# base.net
KiCad netlist of a schematic drawn in EAGLE
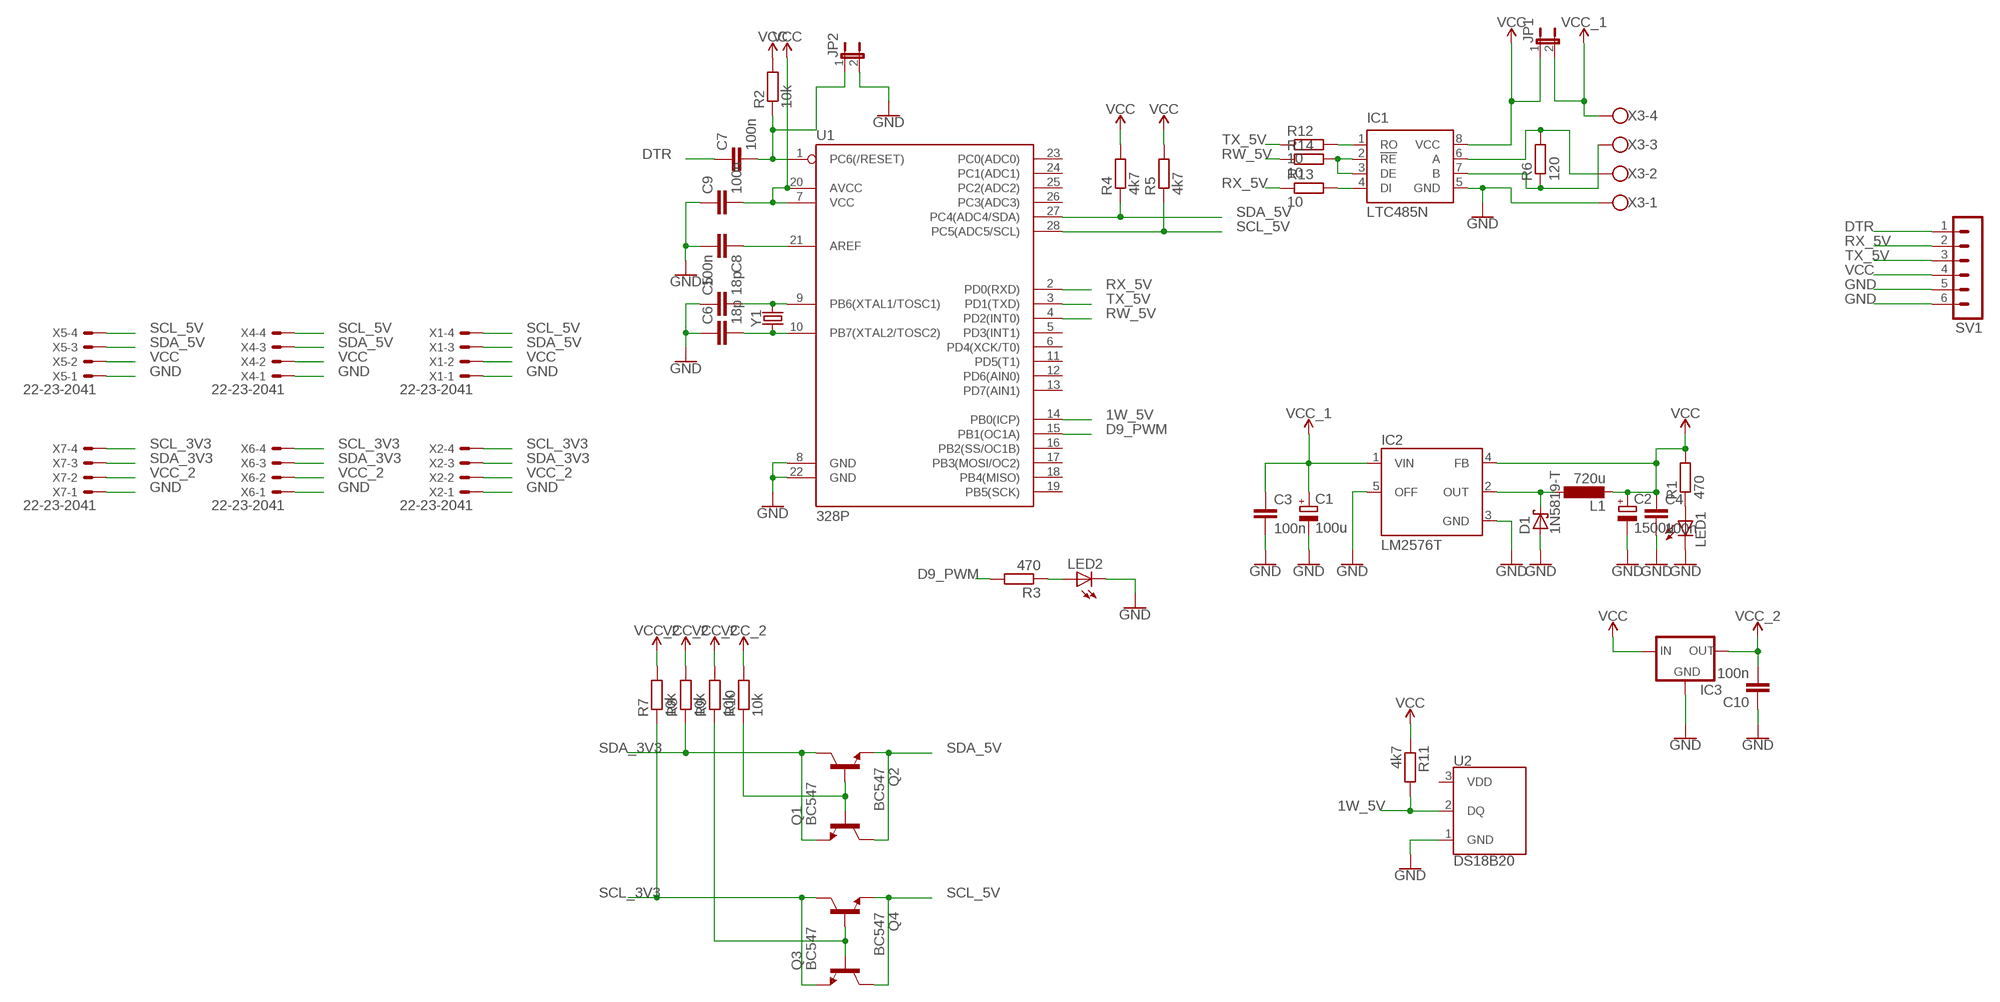
[diagram p0: schematic, sheet 1]

(export (version "E")
  (design (tool "Eeschema 10.0.6"))
  (components
    (comp (ref "C1")
      (value "100u")
      (footprint "eagle-import:E5-10,5")
      (libsource (lib "eagle-import") (part "CPOL-EUE5-10.5"))
    )
    (comp (ref "C2")
      (value "1500u")
      (footprint "eagle-import:E5-10,5")
      (libsource (lib "eagle-import") (part "CPOL-EUE5-10.5"))
    )
    (comp (ref "C3")
      (value "100n")
      (footprint "eagle-import:C025-025X050")
      (libsource (lib "eagle-import") (part "C-EU025-025X050"))
    )
    (comp (ref "C4")
      (value "100n")
      (footprint "eagle-import:C025-025X050")
      (libsource (lib "eagle-import") (part "C-EU025-025X050"))
    )
    (comp (ref "C5")
      (value "18p")
      (footprint "eagle-import:C025-025X050")
      (libsource (lib "eagle-import") (part "C-EU025-025X050"))
    )
    (comp (ref "C6")
      (value "18p")
      (footprint "eagle-import:C025-025X050")
      (libsource (lib "eagle-import") (part "C-EU025-025X050"))
    )
    (comp (ref "C7")
      (value "100n")
      (footprint "eagle-import:C025-025X050")
      (libsource (lib "eagle-import") (part "C-EU025-025X050"))
    )
    (comp (ref "C8")
      (value "100n")
      (footprint "eagle-import:C025-025X050")
      (libsource (lib "eagle-import") (part "C-EU025-025X050"))
    )
    (comp (ref "C9")
      (value "100n")
      (footprint "eagle-import:C025-025X050")
      (libsource (lib "eagle-import") (part "C-EU025-025X050"))
    )
    (comp (ref "C10")
      (value "100n")
      (footprint "eagle-import:C025-025X050")
      (libsource (lib "eagle-import") (part "C-EU025-025X050"))
    )
    (comp (ref "D1")
      (value "1N5819-T")
      (footprint "eagle-import:DO41-7.6")
      (libsource (lib "eagle-import") (part "1N5819-T"))
    )
    (comp (ref "IC1")
      (value "LTC485N")
      (footprint "eagle-import:DIL08")
      (libsource (lib "eagle-import") (part "LTC485N"))
    )
    (comp (ref "IC2")
      (value "LM2576T")
      (footprint "eagle-import:TO220-5")
      (libsource (lib "eagle-import") (part "LM2576T"))
    )
    (comp (ref "IC3")
      (value "78LXX-SOT89")
      (footprint "eagle-import:SOT89")
      (libsource (lib "eagle-import") (part "78LXX-SOT89"))
    )
    (comp (ref "JP1")
      (value "JP1E")
      (footprint "eagle-import:JP1")
      (libsource (lib "eagle-import") (part "JP1E"))
    )
    (comp (ref "JP2")
      (value "JP1E")
      (footprint "eagle-import:JP1")
      (libsource (lib "eagle-import") (part "JP1E"))
    )
    (comp (ref "L1")
      (value "720u")
      (footprint "eagle-import:TJ3-U1")
      (libsource (lib "eagle-import") (part "L-EUTJ3-U1"))
    )
    (comp (ref "LED1")
      (value "LED5MM")
      (footprint "eagle-import:LED5MM")
      (libsource (lib "eagle-import") (part "LED5MM"))
    )
    (comp (ref "LED2")
      (value "LED5MM")
      (footprint "eagle-import:LED5MM")
      (libsource (lib "eagle-import") (part "LED5MM"))
    )
    (comp (ref "Q1")
      (value "BC547")
      (footprint "eagle-import:TO92")
      (libsource (lib "eagle-import") (part "BC547"))
    )
    (comp (ref "Q2")
      (value "BC547")
      (footprint "eagle-import:TO92")
      (libsource (lib "eagle-import") (part "BC547"))
    )
    (comp (ref "Q3")
      (value "BC547")
      (footprint "eagle-import:TO92")
      (libsource (lib "eagle-import") (part "BC547"))
    )
    (comp (ref "Q4")
      (value "BC547")
      (footprint "eagle-import:TO92")
      (libsource (lib "eagle-import") (part "BC547"))
    )
    (comp (ref "R1")
      (value "470")
      (footprint "eagle-import:0204_7")
      (libsource (lib "eagle-import") (part "R-EU_0204/7"))
    )
    (comp (ref "R2")
      (value "10k")
      (footprint "eagle-import:0204_7")
      (libsource (lib "eagle-import") (part "R-EU_0204/7"))
    )
    (comp (ref "R3")
      (value "470")
      (footprint "eagle-import:0204_7")
      (libsource (lib "eagle-import") (part "R-EU_0204/7"))
    )
    (comp (ref "R4")
      (value "4k7")
      (footprint "eagle-import:0204_7")
      (libsource (lib "eagle-import") (part "R-EU_0204/7"))
    )
    (comp (ref "R5")
      (value "4k7")
      (footprint "eagle-import:0204_7")
      (libsource (lib "eagle-import") (part "R-EU_0204/7"))
    )
    (comp (ref "R6")
      (value "120")
      (footprint "eagle-import:0204_7")
      (libsource (lib "eagle-import") (part "R-EU_0204/7"))
    )
    (comp (ref "R7")
      (value "10k")
      (footprint "eagle-import:0204_7")
      (libsource (lib "eagle-import") (part "R-EU_0204/7"))
    )
    (comp (ref "R8")
      (value "10k")
      (footprint "eagle-import:0204_7")
      (libsource (lib "eagle-import") (part "R-EU_0204/7"))
    )
    (comp (ref "R9")
      (value "10k")
      (footprint "eagle-import:0204_7")
      (libsource (lib "eagle-import") (part "R-EU_0204/7"))
    )
    (comp (ref "R10")
      (value "10k")
      (footprint "eagle-import:0204_7")
      (libsource (lib "eagle-import") (part "R-EU_0204/7"))
    )
    (comp (ref "R11")
      (value "4k7")
      (footprint "eagle-import:0204_7")
      (libsource (lib "eagle-import") (part "R-EU_0204/7"))
    )
    (comp (ref "R12")
      (value "10")
      (footprint "eagle-import:0204_7")
      (libsource (lib "eagle-import") (part "R-EU_0204/7"))
    )
    (comp (ref "R13")
      (value "10")
      (footprint "eagle-import:0204_7")
      (libsource (lib "eagle-import") (part "R-EU_0204/7"))
    )
    (comp (ref "R14")
      (value "10")
      (footprint "eagle-import:0204_7")
      (libsource (lib "eagle-import") (part "R-EU_0204/7"))
    )
    (comp (ref "SV1")
      (value "MA06-1")
      (footprint "eagle-import:MA06-1")
      (libsource (lib "eagle-import") (part "MA06-1"))
    )
    (comp (ref "U1")
      (value "328P")
      (footprint "eagle-import:DIP28")
      (libsource (lib "eagle-import") (part "ATMEGA328P_PDIP"))
    )
    (comp (ref "U2")
      (value "DS18B20")
      (footprint "eagle-import:TO-92-AMMO")
      (libsource (lib "eagle-import") (part "DS18B20"))
    )
    (comp (ref "X1")
      (value "22-23-2041")
      (footprint "eagle-import:22-23-2041")
      (fields (field (name "MF") "MOLEX"))
      (libsource (lib "eagle-import") (part "22-23-2041"))
    )
    (comp (ref "X2")
      (value "22-23-2041")
      (footprint "eagle-import:22-23-2041")
      (fields (field (name "MF") "MOLEX"))
      (libsource (lib "eagle-import") (part "22-23-2041"))
    )
    (comp (ref "X3")
      (value "W237-4")
      (footprint "eagle-import:W237-4")
      (libsource (lib "eagle-import") (part "W237-4"))
    )
    (comp (ref "X4")
      (value "22-23-2041")
      (footprint "eagle-import:22-23-2041")
      (fields (field (name "MF") "MOLEX"))
      (libsource (lib "eagle-import") (part "22-23-2041"))
    )
    (comp (ref "X5")
      (value "22-23-2041")
      (footprint "eagle-import:22-23-2041")
      (fields (field (name "MF") "MOLEX"))
      (libsource (lib "eagle-import") (part "22-23-2041"))
    )
    (comp (ref "X6")
      (value "22-23-2041")
      (footprint "eagle-import:22-23-2041")
      (fields (field (name "MF") "MOLEX"))
      (libsource (lib "eagle-import") (part "22-23-2041"))
    )
    (comp (ref "X7")
      (value "22-23-2041")
      (footprint "eagle-import:22-23-2041")
      (fields (field (name "MF") "MOLEX"))
      (libsource (lib "eagle-import") (part "22-23-2041"))
    )
    (comp (ref "Y1")
      (value "CRYSTALPTH-HC49US")
      (footprint "eagle-import:HC49US")
      (libsource (lib "eagle-import") (part "CRYSTALPTH-HC49US"))
    )
  )
  (nets
    (net (code "1") (name "/1W_5V") (class "Default")
      (node (ref "R11") (pin "2") (pinfunction "2_2") (pintype "passive"))
      (node (ref "U1") (pin "14") (pinfunction "PB0(ICP)_14") (pintype "bidirectional"))
      (node (ref "U2") (pin "2") (pinfunction "DQ_2") (pintype "bidirectional"))
    )
    (net (code "2") (name "/D9_PWM") (class "Default")
      (node (ref "R3") (pin "2") (pinfunction "2_2") (pintype "passive"))
      (node (ref "U1") (pin "15") (pinfunction "PB1(OC1A)_15") (pintype "bidirectional"))
    )
    (net (code "3") (name "/DTR") (class "Default")
      (node (ref "C7") (pin "1") (pinfunction "1_1") (pintype "passive"))
      (node (ref "SV1") (pin "1") (pinfunction "1_1") (pintype "passive"))
    )
    (net (code "4") (name "/RW_5V") (class "Default")
      (node (ref "R14") (pin "1") (pinfunction "1_1") (pintype "passive"))
      (node (ref "U1") (pin "4") (pinfunction "PD2(INT0)_4") (pintype "bidirectional"))
    )
    (net (code "5") (name "/RX_5V") (class "Default")
      (node (ref "R13") (pin "1") (pinfunction "1_1") (pintype "passive"))
      (node (ref "SV1") (pin "2") (pinfunction "2_2") (pintype "passive"))
      (node (ref "U1") (pin "2") (pinfunction "PD0(RXD)_2") (pintype "bidirectional"))
    )
    (net (code "6") (name "/SCL_3V3") (class "Default")
      (node (ref "Q3") (pin "3") (pinfunction "C_3") (pintype "passive"))
      (node (ref "Q4") (pin "1") (pinfunction "E_1") (pintype "passive"))
      (node (ref "R7") (pin "1") (pinfunction "1_1") (pintype "passive"))
      (node (ref "X2") (pin "4") (pinfunction "S_4") (pintype "passive"))
      (node (ref "X6") (pin "4") (pinfunction "S_4") (pintype "passive"))
      (node (ref "X7") (pin "4") (pinfunction "S_4") (pintype "passive"))
    )
    (net (code "7") (name "/SCL_5V") (class "Default")
      (node (ref "Q3") (pin "1") (pinfunction "E_1") (pintype "passive"))
      (node (ref "Q4") (pin "3") (pinfunction "C_3") (pintype "passive"))
      (node (ref "R5") (pin "1") (pinfunction "1_1") (pintype "passive"))
      (node (ref "U1") (pin "28") (pinfunction "PC5(ADC5/SCL)_28") (pintype "bidirectional"))
      (node (ref "X1") (pin "4") (pinfunction "S_4") (pintype "passive"))
      (node (ref "X4") (pin "4") (pinfunction "S_4") (pintype "passive"))
      (node (ref "X5") (pin "4") (pinfunction "S_4") (pintype "passive"))
    )
    (net (code "8") (name "/SDA_3V3") (class "Default")
      (node (ref "Q1") (pin "3") (pinfunction "C_3") (pintype "passive"))
      (node (ref "Q2") (pin "1") (pinfunction "E_1") (pintype "passive"))
      (node (ref "R8") (pin "1") (pinfunction "1_1") (pintype "passive"))
      (node (ref "X2") (pin "3") (pinfunction "S_3") (pintype "passive"))
      (node (ref "X6") (pin "3") (pinfunction "S_3") (pintype "passive"))
      (node (ref "X7") (pin "3") (pinfunction "S_3") (pintype "passive"))
    )
    (net (code "9") (name "/SDA_5V") (class "Default")
      (node (ref "Q1") (pin "1") (pinfunction "E_1") (pintype "passive"))
      (node (ref "Q2") (pin "3") (pinfunction "C_3") (pintype "passive"))
      (node (ref "R4") (pin "1") (pinfunction "1_1") (pintype "passive"))
      (node (ref "U1") (pin "27") (pinfunction "PC4(ADC4/SDA)_27") (pintype "bidirectional"))
      (node (ref "X1") (pin "3") (pinfunction "S_3") (pintype "passive"))
      (node (ref "X4") (pin "3") (pinfunction "S_3") (pintype "passive"))
      (node (ref "X5") (pin "3") (pinfunction "S_3") (pintype "passive"))
    )
    (net (code "10") (name "/TX_5V") (class "Default")
      (node (ref "R12") (pin "1") (pinfunction "1_1") (pintype "passive"))
      (node (ref "SV1") (pin "3") (pinfunction "3_3") (pintype "passive"))
      (node (ref "U1") (pin "3") (pinfunction "PD1(TXD)_3") (pintype "bidirectional"))
    )
    (net (code "11") (name "/VDD") (class "Default")
      (node (ref "U2") (pin "3") (pinfunction "VDD_3") (pintype "power_in"))
    )
    (net (code "12") (name "GND") (class "Default")
      (node (ref "C1") (pin "-") (pinfunction "-_-") (pintype "passive"))
      (node (ref "C10") (pin "1") (pinfunction "1_1") (pintype "passive"))
      (node (ref "C2") (pin "-") (pinfunction "-_-") (pintype "passive"))
      (node (ref "C3") (pin "2") (pinfunction "2_2") (pintype "passive"))
      (node (ref "C4") (pin "2") (pinfunction "2_2") (pintype "passive"))
      (node (ref "C5") (pin "1") (pinfunction "1_1") (pintype "passive"))
      (node (ref "C6") (pin "1") (pinfunction "1_1") (pintype "passive"))
      (node (ref "C8") (pin "2") (pinfunction "2_2") (pintype "passive"))
      (node (ref "C9") (pin "1") (pinfunction "1_1") (pintype "passive"))
      (node (ref "D1") (pin "A") (pinfunction "A_A") (pintype "passive"))
      (node (ref "IC1") (pin "5") (pinfunction "GND_5") (pintype "input"))
      (node (ref "IC2") (pin "3") (pinfunction "GND_3") (pintype "power_in"))
      (node (ref "IC2") (pin "5") (pinfunction "OFF_5") (pintype "input"))
      (node (ref "IC3") (pin "2") (pinfunction "GND_2") (pintype "input"))
      (node (ref "JP2") (pin "2") (pinfunction "2_2") (pintype "passive"))
      (node (ref "LED1") (pin "K") (pinfunction "C_K") (pintype "passive"))
      (node (ref "LED2") (pin "K") (pinfunction "C_K") (pintype "passive"))
      (node (ref "SV1") (pin "5") (pinfunction "5_5") (pintype "passive"))
      (node (ref "SV1") (pin "6") (pinfunction "6_6") (pintype "passive"))
      (node (ref "U1") (pin "22") (pinfunction "GND_22") (pintype "bidirectional"))
      (node (ref "U1") (pin "8") (pinfunction "GND_8") (pintype "bidirectional"))
      (node (ref "U2") (pin "1") (pinfunction "GND_1") (pintype "power_in"))
      (node (ref "X1") (pin "1") (pinfunction "S_1") (pintype "passive"))
      (node (ref "X2") (pin "1") (pinfunction "S_1") (pintype "passive"))
      (node (ref "X3") (pin "1") (pinfunction "KL_1") (pintype "passive"))
      (node (ref "X4") (pin "1") (pinfunction "S_1") (pintype "passive"))
      (node (ref "X5") (pin "1") (pinfunction "S_1") (pintype "passive"))
      (node (ref "X6") (pin "1") (pinfunction "S_1") (pintype "passive"))
      (node (ref "X7") (pin "1") (pinfunction "S_1") (pintype "passive"))
    )
    (net (code "13") (name "Net-(IC1-A)") (class "Default")
      (node (ref "IC1") (pin "6") (pinfunction "A_6") (pintype "bidirectional"))
      (node (ref "R6") (pin "2") (pinfunction "2_2") (pintype "passive"))
      (node (ref "X3") (pin "2") (pinfunction "KL_2") (pintype "passive"))
    )
    (net (code "14") (name "Net-(IC1-B)") (class "Default")
      (node (ref "IC1") (pin "7") (pinfunction "B_7") (pintype "bidirectional"))
      (node (ref "R6") (pin "1") (pinfunction "1_1") (pintype "passive"))
      (node (ref "X3") (pin "3") (pinfunction "KL_3") (pintype "passive"))
    )
    (net (code "15") (name "Net-(IC1-DE)") (class "Default")
      (node (ref "IC1") (pin "2") (pinfunction "~{RE}_2") (pintype "input"))
      (node (ref "IC1") (pin "3") (pinfunction "DE_3") (pintype "input"))
      (node (ref "R14") (pin "2") (pinfunction "2_2") (pintype "passive"))
    )
    (net (code "16") (name "Net-(IC1-DI)") (class "Default")
      (node (ref "IC1") (pin "4") (pinfunction "DI_4") (pintype "input"))
      (node (ref "R13") (pin "2") (pinfunction "2_2") (pintype "passive"))
    )
    (net (code "17") (name "Net-(IC1-RO)") (class "Default")
      (node (ref "IC1") (pin "1") (pinfunction "RO_1") (pintype "output"))
      (node (ref "R12") (pin "2") (pinfunction "2_2") (pintype "passive"))
    )
    (net (code "18") (name "Net-(IC2-OUT)") (class "Default")
      (node (ref "D1") (pin "C") (pinfunction "C_C") (pintype "passive"))
      (node (ref "IC2") (pin "2") (pinfunction "OUT_2") (pintype "output"))
      (node (ref "L1") (pin "1") (pinfunction "1_1") (pintype "passive"))
    )
    (net (code "19") (name "Net-(LED1-PadA)") (class "Default")
      (node (ref "LED1") (pin "A") (pinfunction "A_A") (pintype "passive"))
      (node (ref "R1") (pin "1") (pinfunction "1_1") (pintype "passive"))
    )
    (net (code "20") (name "Net-(LED2-PadA)") (class "Default")
      (node (ref "LED2") (pin "A") (pinfunction "A_A") (pintype "passive"))
      (node (ref "R3") (pin "1") (pinfunction "1_1") (pintype "passive"))
    )
    (net (code "21") (name "Net-(Q1-B)") (class "Default")
      (node (ref "Q1") (pin "2") (pinfunction "B_2") (pintype "passive"))
      (node (ref "Q2") (pin "2") (pinfunction "B_2") (pintype "passive"))
      (node (ref "R10") (pin "1") (pinfunction "1_1") (pintype "passive"))
    )
    (net (code "22") (name "Net-(Q3-B)") (class "Default")
      (node (ref "Q3") (pin "2") (pinfunction "B_2") (pintype "passive"))
      (node (ref "Q4") (pin "2") (pinfunction "B_2") (pintype "passive"))
      (node (ref "R9") (pin "1") (pinfunction "1_1") (pintype "passive"))
    )
    (net (code "23") (name "Net-(U1-AREF)") (class "Default")
      (node (ref "C8") (pin "1") (pinfunction "1_1") (pintype "passive"))
      (node (ref "U1") (pin "21") (pinfunction "AREF_21") (pintype "bidirectional"))
    )
    (net (code "24") (name "Net-(U1-PB6(XTAL1{slash}TOSC1))") (class "Default")
      (node (ref "C5") (pin "2") (pinfunction "2_2") (pintype "passive"))
      (node (ref "U1") (pin "9") (pinfunction "PB6(XTAL1/TOSC1)_9") (pintype "bidirectional"))
      (node (ref "Y1") (pin "2") (pinfunction "2_2") (pintype "passive"))
    )
    (net (code "25") (name "Net-(U1-PB7(XTAL2{slash}TOSC2))") (class "Default")
      (node (ref "C6") (pin "2") (pinfunction "2_2") (pintype "passive"))
      (node (ref "U1") (pin "10") (pinfunction "PB7(XTAL2/TOSC2)_10") (pintype "bidirectional"))
      (node (ref "Y1") (pin "1") (pinfunction "1_1") (pintype "passive"))
    )
    (net (code "26") (name "Net-(U1-PC6({slash}RESET))") (class "Default")
      (node (ref "C7") (pin "2") (pinfunction "2_2") (pintype "passive"))
      (node (ref "JP2") (pin "1") (pinfunction "1_1") (pintype "passive"))
      (node (ref "R2") (pin "1") (pinfunction "1_1") (pintype "passive"))
      (node (ref "U1") (pin "1") (pinfunction "PC6(/RESET)_1") (pintype "bidirectional"))
    )
    (net (code "27") (name "VCC") (class "Default")
      (node (ref "C2") (pin "+") (pinfunction "+_+") (pintype "passive"))
      (node (ref "C4") (pin "1") (pinfunction "1_1") (pintype "passive"))
      (node (ref "C9") (pin "2") (pinfunction "2_2") (pintype "passive"))
      (node (ref "IC1") (pin "8") (pinfunction "VCC_8") (pintype "input"))
      (node (ref "IC2") (pin "4") (pinfunction "FB_4") (pintype "input"))
      (node (ref "IC3") (pin "3") (pinfunction "IN_3") (pintype "input"))
      (node (ref "JP1") (pin "1") (pinfunction "1_1") (pintype "passive"))
      (node (ref "L1") (pin "2") (pinfunction "2_2") (pintype "passive"))
      (node (ref "R1") (pin "2") (pinfunction "2_2") (pintype "passive"))
      (node (ref "R11") (pin "1") (pinfunction "1_1") (pintype "passive"))
      (node (ref "R2") (pin "2") (pinfunction "2_2") (pintype "passive"))
      (node (ref "R4") (pin "2") (pinfunction "2_2") (pintype "passive"))
      (node (ref "R5") (pin "2") (pinfunction "2_2") (pintype "passive"))
      (node (ref "SV1") (pin "4") (pinfunction "4_4") (pintype "passive"))
      (node (ref "U1") (pin "20") (pinfunction "AVCC_20") (pintype "bidirectional"))
      (node (ref "U1") (pin "7") (pinfunction "VCC_7") (pintype "bidirectional"))
      (node (ref "X1") (pin "2") (pinfunction "S_2") (pintype "passive"))
      (node (ref "X4") (pin "2") (pinfunction "S_2") (pintype "passive"))
      (node (ref "X5") (pin "2") (pinfunction "S_2") (pintype "passive"))
    )
    (net (code "28") (name "VCC_1") (class "Default")
      (node (ref "C1") (pin "+") (pinfunction "+_+") (pintype "passive"))
      (node (ref "C3") (pin "1") (pinfunction "1_1") (pintype "passive"))
      (node (ref "IC2") (pin "1") (pinfunction "VIN_1") (pintype "power_in"))
      (node (ref "JP1") (pin "2") (pinfunction "2_2") (pintype "passive"))
      (node (ref "X3") (pin "4") (pinfunction "KL_4") (pintype "passive"))
    )
    (net (code "29") (name "VCC_2") (class "Default")
      (node (ref "C10") (pin "2") (pinfunction "2_2") (pintype "passive"))
      (node (ref "IC3") (pin "1") (pinfunction "OUT_1") (pintype "passive"))
      (node (ref "R10") (pin "2") (pinfunction "2_2") (pintype "passive"))
      (node (ref "R7") (pin "2") (pinfunction "2_2") (pintype "passive"))
      (node (ref "R8") (pin "2") (pinfunction "2_2") (pintype "passive"))
      (node (ref "R9") (pin "2") (pinfunction "2_2") (pintype "passive"))
      (node (ref "X2") (pin "2") (pinfunction "S_2") (pintype "passive"))
      (node (ref "X6") (pin "2") (pinfunction "S_2") (pintype "passive"))
      (node (ref "X7") (pin "2") (pinfunction "S_2") (pintype "passive"))
    )
    (net (code "30") (name "unconnected-(U1-PB2(SS{slash}OC1B)-Pad16)") (class "Default")
      (node (ref "U1") (pin "16") (pinfunction "PB2(SS/OC1B)_16") (pintype "bidirectional"))
    )
    (net (code "31") (name "unconnected-(U1-PB3(MOSI{slash}OC2)-Pad17)") (class "Default")
      (node (ref "U1") (pin "17") (pinfunction "PB3(MOSI/OC2)_17") (pintype "bidirectional"))
    )
    (net (code "32") (name "unconnected-(U1-PB4(MISO)-Pad18)") (class "Default")
      (node (ref "U1") (pin "18") (pinfunction "PB4(MISO)_18") (pintype "bidirectional"))
    )
    (net (code "33") (name "unconnected-(U1-PB5(SCK)-Pad19)") (class "Default")
      (node (ref "U1") (pin "19") (pinfunction "PB5(SCK)_19") (pintype "bidirectional"))
    )
    (net (code "34") (name "unconnected-(U1-PC0(ADC0)-Pad23)") (class "Default")
      (node (ref "U1") (pin "23") (pinfunction "PC0(ADC0)_23") (pintype "bidirectional"))
    )
    (net (code "35") (name "unconnected-(U1-PC1(ADC1)-Pad24)") (class "Default")
      (node (ref "U1") (pin "24") (pinfunction "PC1(ADC1)_24") (pintype "bidirectional"))
    )
    (net (code "36") (name "unconnected-(U1-PC2(ADC2)-Pad25)") (class "Default")
      (node (ref "U1") (pin "25") (pinfunction "PC2(ADC2)_25") (pintype "bidirectional"))
    )
    (net (code "37") (name "unconnected-(U1-PC3(ADC3)-Pad26)") (class "Default")
      (node (ref "U1") (pin "26") (pinfunction "PC3(ADC3)_26") (pintype "bidirectional"))
    )
    (net (code "38") (name "unconnected-(U1-PD3(INT1)-Pad5)") (class "Default")
      (node (ref "U1") (pin "5") (pinfunction "PD3(INT1)_5") (pintype "bidirectional"))
    )
    (net (code "39") (name "unconnected-(U1-PD4(XCK{slash}T0)-Pad6)") (class "Default")
      (node (ref "U1") (pin "6") (pinfunction "PD4(XCK/T0)_6") (pintype "bidirectional"))
    )
    (net (code "40") (name "unconnected-(U1-PD5(T1)-Pad11)") (class "Default")
      (node (ref "U1") (pin "11") (pinfunction "PD5(T1)_11") (pintype "bidirectional"))
    )
    (net (code "41") (name "unconnected-(U1-PD6(AIN0)-Pad12)") (class "Default")
      (node (ref "U1") (pin "12") (pinfunction "PD6(AIN0)_12") (pintype "bidirectional"))
    )
    (net (code "42") (name "unconnected-(U1-PD7(AIN1)-Pad13)") (class "Default")
      (node (ref "U1") (pin "13") (pinfunction "PD7(AIN1)_13") (pintype "bidirectional"))
    )
  )
)
